# USB.net
KiCad netlist of a schematic drawn in Altium Designer
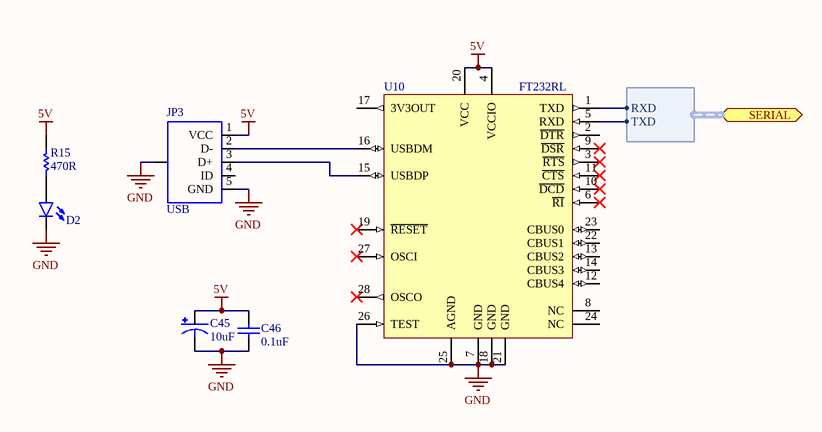
[diagram p0: USB.SchDoc]

(export (version "E")
  (design (tool "Eeschema 10.0.6"))
  (components
    (comp (ref "C45")
      (value "10uF")
      (footprint "CPOL-RADIAL")
      (libsource (lib "Components") (part "PolarizedCap"))
    )
    (comp (ref "C46") (value "0.1uF") (footprint "CAP-PTH") (libsource (lib "Components") (part "Cap")))
    (comp (ref "D2")
      (value "LED")
      (footprint "LED5MM")
      (fields (field (name "PARTNUMBER") "LTST-C193TGKT-5A") (field (name "MANUFACTURER") "Lite-On Inc."))
      (libsource (lib "Components") (part "LED"))
    )
    (comp (ref "JP3")
      (value "USB")
      (footprint "USB-MICROB")
      (fields (field (name "PARTNUMBER") "10118192-0001LF") (field (name "MANUFACTURER") "Amphenol FCI"))
      (libsource (lib "Connectors") (part "USB_MICROB_SMT"))
    )
    (comp (ref "R15") (value "470R") (footprint "RESISTOR") (libsource (lib "Components") (part "Resistor")))
    (comp (ref "U10")
      (value "FT232RL")
      (footprint "SSOP-28_N")
      (description "USB UART Asynchronous Serial Data Transfer Chip, 28-pin SSOP, Tube")
      (fields (field (name "PARTNUMBER") "FT232RL-Tube") (field (name "MANUFACTURER") "FTDI"))
      (libsource (lib "Altium Content Vault") (part "COM-UART-FT232R-IL28"))
    )
  )
  (nets
    (net (code "2") (name "/RXD") (class "Default")
      (node (ref "U10") (pin "1") (pinfunction "TXD_1") (pintype "output"))
    )
    (net (code "3") (name "/TXD") (class "Default")
      (node (ref "U10") (pin "5") (pinfunction "RXD_5") (pintype "input"))
    )
    (net (code "5") (name "5V") (class "Default")
      (node (ref "C45") (pin "1") (pinfunction "+_1") (pintype "passive"))
      (node (ref "C46") (pin "1") (pinfunction "1_1") (pintype "passive"))
      (node (ref "JP3") (pin "1") (pinfunction "VCC_1") (pintype "passive"))
      (node (ref "R15") (pin "1") (pinfunction "1_1") (pintype "passive"))
      (node (ref "U10") (pin "20") (pinfunction "VCC_20") (pintype "power_in"))
      (node (ref "U10") (pin "4") (pinfunction "VCCIO_4") (pintype "power_in"))
    )
    (net (code "6") (name "GND") (class "Default")
      (node (ref "C45") (pin "2") (pinfunction "-_2") (pintype "passive"))
      (node (ref "C46") (pin "2") (pinfunction "2_2") (pintype "passive"))
      (node (ref "D2") (pin "K") (pinfunction "K_K") (pintype "passive"))
      (node (ref "JP3") (pin "5") (pinfunction "GND_5") (pintype "passive"))
      (node (ref "JP3") (pin "6") (pinfunction "SHIELD_6") (pintype "passive"))
      (node (ref "U10") (pin "18") (pinfunction "GND_18") (pintype "power_in"))
      (node (ref "U10") (pin "21") (pinfunction "GND_21") (pintype "power_in"))
      (node (ref "U10") (pin "25") (pinfunction "AGND_25") (pintype "power_in"))
      (node (ref "U10") (pin "26") (pinfunction "TEST_26") (pintype "input"))
      (node (ref "U10") (pin "7") (pinfunction "GND_7") (pintype "power_in"))
    )
    (net (code "7") (name "Net-(D2-PadA)") (class "Default")
      (node (ref "D2") (pin "A") (pinfunction "A_A") (pintype "passive"))
      (node (ref "R15") (pin "2") (pinfunction "2_2") (pintype "passive"))
    )
    (net (code "8") (name "Net-(JP3-D+)") (class "Default")
      (node (ref "JP3") (pin "3") (pinfunction "D+_3") (pintype "passive"))
      (node (ref "U10") (pin "15") (pinfunction "USBDP_15") (pintype "bidirectional"))
    )
    (net (code "9") (name "Net-(JP3-D-)") (class "Default")
      (node (ref "JP3") (pin "2") (pinfunction "D-_2") (pintype "passive"))
      (node (ref "U10") (pin "16") (pinfunction "USBDM_16") (pintype "bidirectional"))
    )
    (net (code "10") (name "unconnected-(JP3-ID-Pad4)") (class "Default")
      (node (ref "JP3") (pin "4") (pinfunction "ID_4") (pintype "passive"))
    )
    (net (code "11") (name "unconnected-(U10-3V3OUT-Pad17)") (class "Default")
      (node (ref "U10") (pin "17") (pinfunction "3V3OUT_17") (pintype "output"))
    )
    (net (code "12") (name "unconnected-(U10-CBUS0-Pad23)") (class "Default")
      (node (ref "U10") (pin "23") (pinfunction "CBUS0_23") (pintype "bidirectional"))
    )
    (net (code "13") (name "unconnected-(U10-CBUS1-Pad22)") (class "Default")
      (node (ref "U10") (pin "22") (pinfunction "CBUS1_22") (pintype "bidirectional"))
    )
    (net (code "14") (name "unconnected-(U10-CBUS2-Pad13)") (class "Default")
      (node (ref "U10") (pin "13") (pinfunction "CBUS2_13") (pintype "bidirectional"))
    )
    (net (code "15") (name "unconnected-(U10-CBUS3-Pad14)") (class "Default")
      (node (ref "U10") (pin "14") (pinfunction "CBUS3_14") (pintype "bidirectional"))
    )
    (net (code "16") (name "unconnected-(U10-CBUS4-Pad12)") (class "Default")
      (node (ref "U10") (pin "12") (pinfunction "CBUS4_12") (pintype "bidirectional"))
    )
    (net (code "17") (name "unconnected-(U10-NC-Pad8)") (class "Default")
      (node (ref "U10") (pin "8") (pinfunction "NC_8") (pintype "passive"))
    )
    (net (code "18") (name "unconnected-(U10-NC-Pad24)") (class "Default")
      (node (ref "U10") (pin "24") (pinfunction "NC_24") (pintype "passive"))
    )
    (net (code "19") (name "unconnected-(U10-OSCI-Pad27)") (class "Default")
      (node (ref "U10") (pin "27") (pinfunction "OSCI_27") (pintype "input+no_connect"))
    )
    (net (code "20") (name "unconnected-(U10-OSCO-Pad28)") (class "Default")
      (node (ref "U10") (pin "28") (pinfunction "OSCO_28") (pintype "output+no_connect"))
    )
    (net (code "21") (name "unconnected-(U10-~{CTS}-Pad11)") (class "Default")
      (node (ref "U10") (pin "11") (pinfunction "~{CTS}_11") (pintype "input+no_connect"))
    )
    (net (code "22") (name "unconnected-(U10-~{DCD}-Pad10)") (class "Default")
      (node (ref "U10") (pin "10") (pinfunction "~{DCD}_10") (pintype "input+no_connect"))
    )
    (net (code "23") (name "unconnected-(U10-~{DSR}-Pad9)") (class "Default")
      (node (ref "U10") (pin "9") (pinfunction "~{DSR}_9") (pintype "input+no_connect"))
    )
    (net (code "24") (name "unconnected-(U10-~{DTR}-Pad2)") (class "Default")
      (node (ref "U10") (pin "2") (pinfunction "~{DTR}_2") (pintype "output"))
    )
    (net (code "25") (name "unconnected-(U10-~{RESET}-Pad19)") (class "Default")
      (node (ref "U10") (pin "19") (pinfunction "~{RESET}_19") (pintype "input+no_connect"))
    )
    (net (code "26") (name "unconnected-(U10-~{RI}-Pad6)") (class "Default")
      (node (ref "U10") (pin "6") (pinfunction "~{RI}_6") (pintype "input+no_connect"))
    )
    (net (code "27") (name "unconnected-(U10-~{RTS}-Pad3)") (class "Default")
      (node (ref "U10") (pin "3") (pinfunction "~{RTS}_3") (pintype "output+no_connect"))
    )
  )
)
